# Analog_Ball_Sensor.net
KiCad netlist of a schematic drawn in Altium Designer
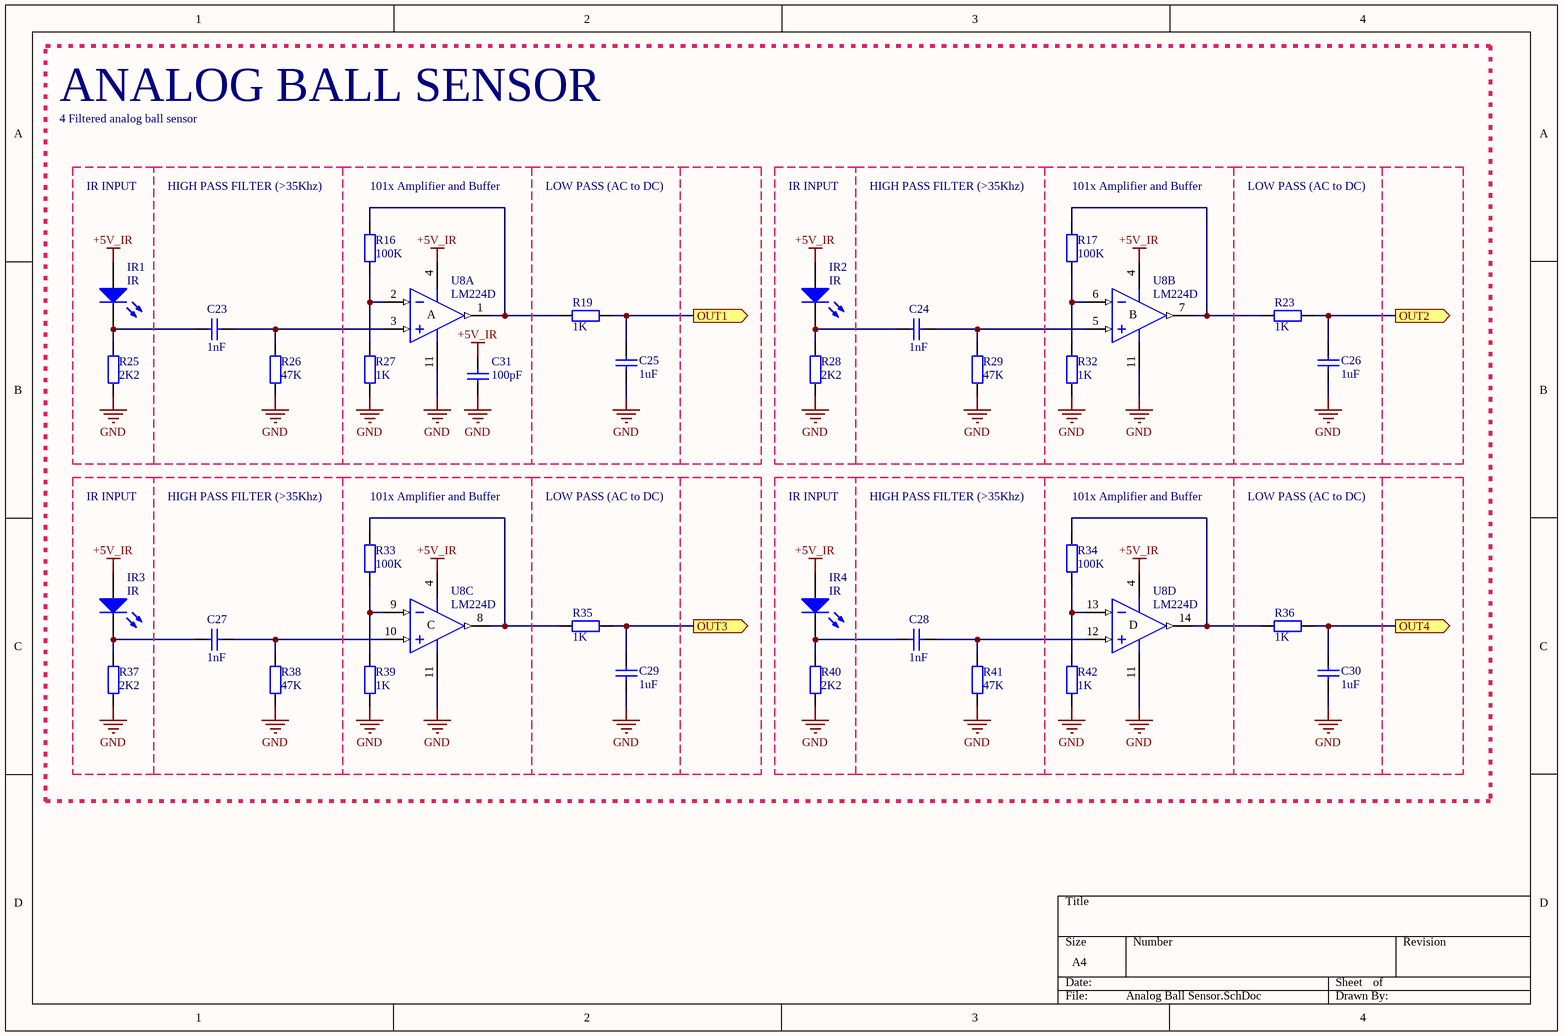
[diagram p0: Analog Ball Sensor.SchDoc]

(export (version "E")
  (design (tool "Eeschema 10.0.6"))
  (components
    (comp (ref "C23")
      (value "1nF")
      (footprint "C0805")
      (description "Capacitor (Semiconductor SIM Model)")
      (fields (field (name "PUBLISHER") "Altium Limited"))
      (libsource (lib "Miscellaneous Devices") (part "Cap Semi"))
    )
    (comp (ref "C24")
      (value "1nF")
      (footprint "C0805")
      (description "Capacitor (Semiconductor SIM Model)")
      (fields (field (name "PUBLISHER") "Altium Limited"))
      (libsource (lib "Miscellaneous Devices") (part "Cap Semi"))
    )
    (comp (ref "C25")
      (value "1uF")
      (footprint "C0805")
      (description "Capacitor (Semiconductor SIM Model)")
      (fields (field (name "PUBLISHER") "Altium Limited"))
      (libsource (lib "Miscellaneous Devices") (part "Cap Semi"))
    )
    (comp (ref "C26")
      (value "1uF")
      (footprint "C0805")
      (description "Capacitor (Semiconductor SIM Model)")
      (fields (field (name "PUBLISHER") "Altium Limited"))
      (libsource (lib "Miscellaneous Devices") (part "Cap Semi"))
    )
    (comp (ref "C27")
      (value "1nF")
      (footprint "C0805")
      (description "Capacitor (Semiconductor SIM Model)")
      (fields (field (name "PUBLISHER") "Altium Limited"))
      (libsource (lib "Miscellaneous Devices") (part "Cap Semi"))
    )
    (comp (ref "C28")
      (value "1nF")
      (footprint "C0805")
      (description "Capacitor (Semiconductor SIM Model)")
      (fields (field (name "PUBLISHER") "Altium Limited"))
      (libsource (lib "Miscellaneous Devices") (part "Cap Semi"))
    )
    (comp (ref "C29")
      (value "1uF")
      (footprint "C0805")
      (description "Capacitor (Semiconductor SIM Model)")
      (fields (field (name "PUBLISHER") "Altium Limited"))
      (libsource (lib "Miscellaneous Devices") (part "Cap Semi"))
    )
    (comp (ref "C30")
      (value "1uF")
      (footprint "C0805")
      (description "Capacitor (Semiconductor SIM Model)")
      (fields (field (name "PUBLISHER") "Altium Limited"))
      (libsource (lib "Miscellaneous Devices") (part "Cap Semi"))
    )
    (comp (ref "C31")
      (value "100pF")
      (footprint "6-0805_N")
      (description "Capacitor (Semiconductor SIM Model)")
      (fields (field (name "Comment") "Cap Semi") (field (name "PUBLISHER") "Altium Limited"))
      (libsource (lib "Miscellaneous Devices") (part "Cap Semi"))
    )
    (comp (ref "IR1")
      (value "IR")
      (footprint "LED-5mm - Horizontal")
      (libsource (lib "CustomLibrary") (part "LED"))
    )
    (comp (ref "IR2")
      (value "IR")
      (footprint "LED-5mm - Horizontal")
      (libsource (lib "CustomLibrary") (part "LED"))
    )
    (comp (ref "IR3")
      (value "IR")
      (footprint "LED-5mm - Horizontal")
      (libsource (lib "CustomLibrary") (part "LED"))
    )
    (comp (ref "IR4")
      (value "IR")
      (footprint "LED-5mm - Horizontal")
      (libsource (lib "CustomLibrary") (part "LED"))
    )
    (comp (ref "R16") (value "100K") (footprint "RES1206") (libsource (lib "CustomLibrary") (part "RES")))
    (comp (ref "R17") (value "100K") (footprint "RES1206") (libsource (lib "CustomLibrary") (part "RES")))
    (comp (ref "R19") (value "1K") (footprint "RES1206") (libsource (lib "") (part "RES_1")))
    (comp (ref "R23") (value "1K") (footprint "RES1206") (libsource (lib "") (part "RES_1")))
    (comp (ref "R25") (value "2K2") (footprint "RES1206") (libsource (lib "") (part "RES_2")))
    (comp (ref "R26") (value "47K") (footprint "RES1206") (libsource (lib "CustomLibrary") (part "RES")))
    (comp (ref "R27") (value "1K") (footprint "RES1206") (libsource (lib "CustomLibrary") (part "RES")))
    (comp (ref "R28") (value "2K2") (footprint "RES1206") (libsource (lib "") (part "RES_2")))
    (comp (ref "R29") (value "47K") (footprint "RES1206") (libsource (lib "CustomLibrary") (part "RES")))
    (comp (ref "R32") (value "1K") (footprint "RES1206") (libsource (lib "CustomLibrary") (part "RES")))
    (comp (ref "R33") (value "100K") (footprint "RES1206") (libsource (lib "CustomLibrary") (part "RES")))
    (comp (ref "R34") (value "100K") (footprint "RES1206") (libsource (lib "CustomLibrary") (part "RES")))
    (comp (ref "R35") (value "1K") (footprint "RES1206") (libsource (lib "") (part "RES_1")))
    (comp (ref "R36") (value "1K") (footprint "RES1206") (libsource (lib "") (part "RES_1")))
    (comp (ref "R37") (value "2K2") (footprint "RES1206") (libsource (lib "") (part "RES_2")))
    (comp (ref "R38") (value "47K") (footprint "RES1206") (libsource (lib "CustomLibrary") (part "RES")))
    (comp (ref "R39") (value "1K") (footprint "RES1206") (libsource (lib "CustomLibrary") (part "RES")))
    (comp (ref "R40") (value "2K2") (footprint "RES1206") (libsource (lib "") (part "RES_2")))
    (comp (ref "R41") (value "47K") (footprint "RES1206") (libsource (lib "CustomLibrary") (part "RES")))
    (comp (ref "R42") (value "1K") (footprint "RES1206") (libsource (lib "CustomLibrary") (part "RES")))
    (comp (ref "U8")
      (value "LM224D")
      (footprint "SO14_N")
      (description "Low-Power Quad Operational Amplifier")
      (fields (field (name "PUBLISHER") "Altium Limited"))
      (libsource (lib "ST Operational Amplifier") (part "LM224D"))
    )
  )
  (nets
    (net (code "1") (name "+5V_IR") (class "Default")
      (node (ref "C31") (pin "2") (pinfunction "2_2") (pintype "passive"))
      (node (ref "IR1") (pin "1") (pinfunction "A_1") (pintype "passive"))
      (node (ref "IR2") (pin "1") (pinfunction "A_1") (pintype "passive"))
      (node (ref "IR3") (pin "1") (pinfunction "A_1") (pintype "passive"))
      (node (ref "IR4") (pin "1") (pinfunction "A_1") (pintype "passive"))
      (node (ref "U8") (pin "4") (pinfunction "V+_4") (pintype "power_in"))
    )
    (net (code "2") (name "/OUT1") (class "Default")
      (node (ref "C25") (pin "1") (pinfunction "1_1") (pintype "passive"))
      (node (ref "R19") (pin "2") (pinfunction "2_2") (pintype "passive"))
    )
    (net (code "3") (name "/OUT2") (class "Default")
      (node (ref "C26") (pin "1") (pinfunction "1_1") (pintype "passive"))
      (node (ref "R23") (pin "2") (pinfunction "2_2") (pintype "passive"))
    )
    (net (code "4") (name "/OUT3") (class "Default")
      (node (ref "C29") (pin "1") (pinfunction "1_1") (pintype "passive"))
      (node (ref "R35") (pin "2") (pinfunction "2_2") (pintype "passive"))
    )
    (net (code "5") (name "/OUT4") (class "Default")
      (node (ref "C30") (pin "1") (pinfunction "1_1") (pintype "passive"))
      (node (ref "R36") (pin "2") (pinfunction "2_2") (pintype "passive"))
    )
    (net (code "6") (name "GND") (class "Default")
      (node (ref "C25") (pin "2") (pinfunction "2_2") (pintype "passive"))
      (node (ref "C26") (pin "2") (pinfunction "2_2") (pintype "passive"))
      (node (ref "C29") (pin "2") (pinfunction "2_2") (pintype "passive"))
      (node (ref "C30") (pin "2") (pinfunction "2_2") (pintype "passive"))
      (node (ref "C31") (pin "1") (pinfunction "1_1") (pintype "passive"))
      (node (ref "R25") (pin "1") (pinfunction "1_1") (pintype "passive"))
      (node (ref "R26") (pin "2") (pinfunction "2_2") (pintype "passive"))
      (node (ref "R27") (pin "2") (pinfunction "2_2") (pintype "passive"))
      (node (ref "R28") (pin "1") (pinfunction "1_1") (pintype "passive"))
      (node (ref "R29") (pin "2") (pinfunction "2_2") (pintype "passive"))
      (node (ref "R32") (pin "2") (pinfunction "2_2") (pintype "passive"))
      (node (ref "R37") (pin "1") (pinfunction "1_1") (pintype "passive"))
      (node (ref "R38") (pin "2") (pinfunction "2_2") (pintype "passive"))
      (node (ref "R39") (pin "2") (pinfunction "2_2") (pintype "passive"))
      (node (ref "R40") (pin "1") (pinfunction "1_1") (pintype "passive"))
      (node (ref "R41") (pin "2") (pinfunction "2_2") (pintype "passive"))
      (node (ref "R42") (pin "2") (pinfunction "2_2") (pintype "passive"))
      (node (ref "U8") (pin "11") (pinfunction "V-_11") (pintype "power_in"))
    )
    (net (code "7") (name "Net-(IR1-K)") (class "Default")
      (node (ref "C23") (pin "2") (pinfunction "2_2") (pintype "passive"))
      (node (ref "IR1") (pin "2") (pinfunction "K_2") (pintype "passive"))
      (node (ref "R25") (pin "2") (pinfunction "2_2") (pintype "passive"))
    )
    (net (code "8") (name "Net-(IR2-K)") (class "Default")
      (node (ref "C24") (pin "2") (pinfunction "2_2") (pintype "passive"))
      (node (ref "IR2") (pin "2") (pinfunction "K_2") (pintype "passive"))
      (node (ref "R28") (pin "2") (pinfunction "2_2") (pintype "passive"))
    )
    (net (code "9") (name "Net-(IR3-K)") (class "Default")
      (node (ref "C27") (pin "2") (pinfunction "2_2") (pintype "passive"))
      (node (ref "IR3") (pin "2") (pinfunction "K_2") (pintype "passive"))
      (node (ref "R37") (pin "2") (pinfunction "2_2") (pintype "passive"))
    )
    (net (code "10") (name "Net-(IR4-K)") (class "Default")
      (node (ref "C28") (pin "2") (pinfunction "2_2") (pintype "passive"))
      (node (ref "IR4") (pin "2") (pinfunction "K_2") (pintype "passive"))
      (node (ref "R40") (pin "2") (pinfunction "2_2") (pintype "passive"))
    )
    (net (code "11") (name "Net-(U8A-IN+)") (class "Default")
      (node (ref "C23") (pin "1") (pinfunction "1_1") (pintype "passive"))
      (node (ref "R26") (pin "1") (pinfunction "1_1") (pintype "passive"))
      (node (ref "U8") (pin "3") (pinfunction "IN+_3") (pintype "input"))
    )
    (net (code "12") (name "Net-(U8A-IN-)") (class "Default")
      (node (ref "R16") (pin "2") (pinfunction "2_2") (pintype "passive"))
      (node (ref "R27") (pin "1") (pinfunction "1_1") (pintype "passive"))
      (node (ref "U8") (pin "2") (pinfunction "IN-_2") (pintype "input"))
    )
    (net (code "13") (name "Net-(U8A-OUT)") (class "Default")
      (node (ref "R16") (pin "1") (pinfunction "1_1") (pintype "passive"))
      (node (ref "R19") (pin "1") (pinfunction "1_1") (pintype "passive"))
      (node (ref "U8") (pin "1") (pinfunction "OUT_1") (pintype "output"))
    )
    (net (code "14") (name "Net-(U8B-IN+)") (class "Default")
      (node (ref "C24") (pin "1") (pinfunction "1_1") (pintype "passive"))
      (node (ref "R29") (pin "1") (pinfunction "1_1") (pintype "passive"))
      (node (ref "U8") (pin "5") (pinfunction "IN+_5") (pintype "input"))
    )
    (net (code "15") (name "Net-(U8B-IN-)") (class "Default")
      (node (ref "R17") (pin "2") (pinfunction "2_2") (pintype "passive"))
      (node (ref "R32") (pin "1") (pinfunction "1_1") (pintype "passive"))
      (node (ref "U8") (pin "6") (pinfunction "IN-_6") (pintype "input"))
    )
    (net (code "16") (name "Net-(U8B-OUT)") (class "Default")
      (node (ref "R17") (pin "1") (pinfunction "1_1") (pintype "passive"))
      (node (ref "R23") (pin "1") (pinfunction "1_1") (pintype "passive"))
      (node (ref "U8") (pin "7") (pinfunction "OUT_7") (pintype "output"))
    )
    (net (code "17") (name "Net-(U8C-IN+)") (class "Default")
      (node (ref "C27") (pin "1") (pinfunction "1_1") (pintype "passive"))
      (node (ref "R38") (pin "1") (pinfunction "1_1") (pintype "passive"))
      (node (ref "U8") (pin "10") (pinfunction "IN+_10") (pintype "input"))
    )
    (net (code "18") (name "Net-(U8C-IN-)") (class "Default")
      (node (ref "R33") (pin "2") (pinfunction "2_2") (pintype "passive"))
      (node (ref "R39") (pin "1") (pinfunction "1_1") (pintype "passive"))
      (node (ref "U8") (pin "9") (pinfunction "IN-_9") (pintype "input"))
    )
    (net (code "19") (name "Net-(U8C-OUT)") (class "Default")
      (node (ref "R33") (pin "1") (pinfunction "1_1") (pintype "passive"))
      (node (ref "R35") (pin "1") (pinfunction "1_1") (pintype "passive"))
      (node (ref "U8") (pin "8") (pinfunction "OUT_8") (pintype "output"))
    )
    (net (code "20") (name "Net-(U8D-IN+)") (class "Default")
      (node (ref "C28") (pin "1") (pinfunction "1_1") (pintype "passive"))
      (node (ref "R41") (pin "1") (pinfunction "1_1") (pintype "passive"))
      (node (ref "U8") (pin "12") (pinfunction "IN+_12") (pintype "input"))
    )
    (net (code "21") (name "Net-(U8D-IN-)") (class "Default")
      (node (ref "R34") (pin "2") (pinfunction "2_2") (pintype "passive"))
      (node (ref "R42") (pin "1") (pinfunction "1_1") (pintype "passive"))
      (node (ref "U8") (pin "13") (pinfunction "IN-_13") (pintype "input"))
    )
    (net (code "22") (name "Net-(U8D-OUT)") (class "Default")
      (node (ref "R34") (pin "1") (pinfunction "1_1") (pintype "passive"))
      (node (ref "R36") (pin "1") (pinfunction "1_1") (pintype "passive"))
      (node (ref "U8") (pin "14") (pinfunction "OUT_14") (pintype "output"))
    )
  )
)
